# Turnstile_ZpC.net
KiCad netlist of a schematic drawn in EAGLE
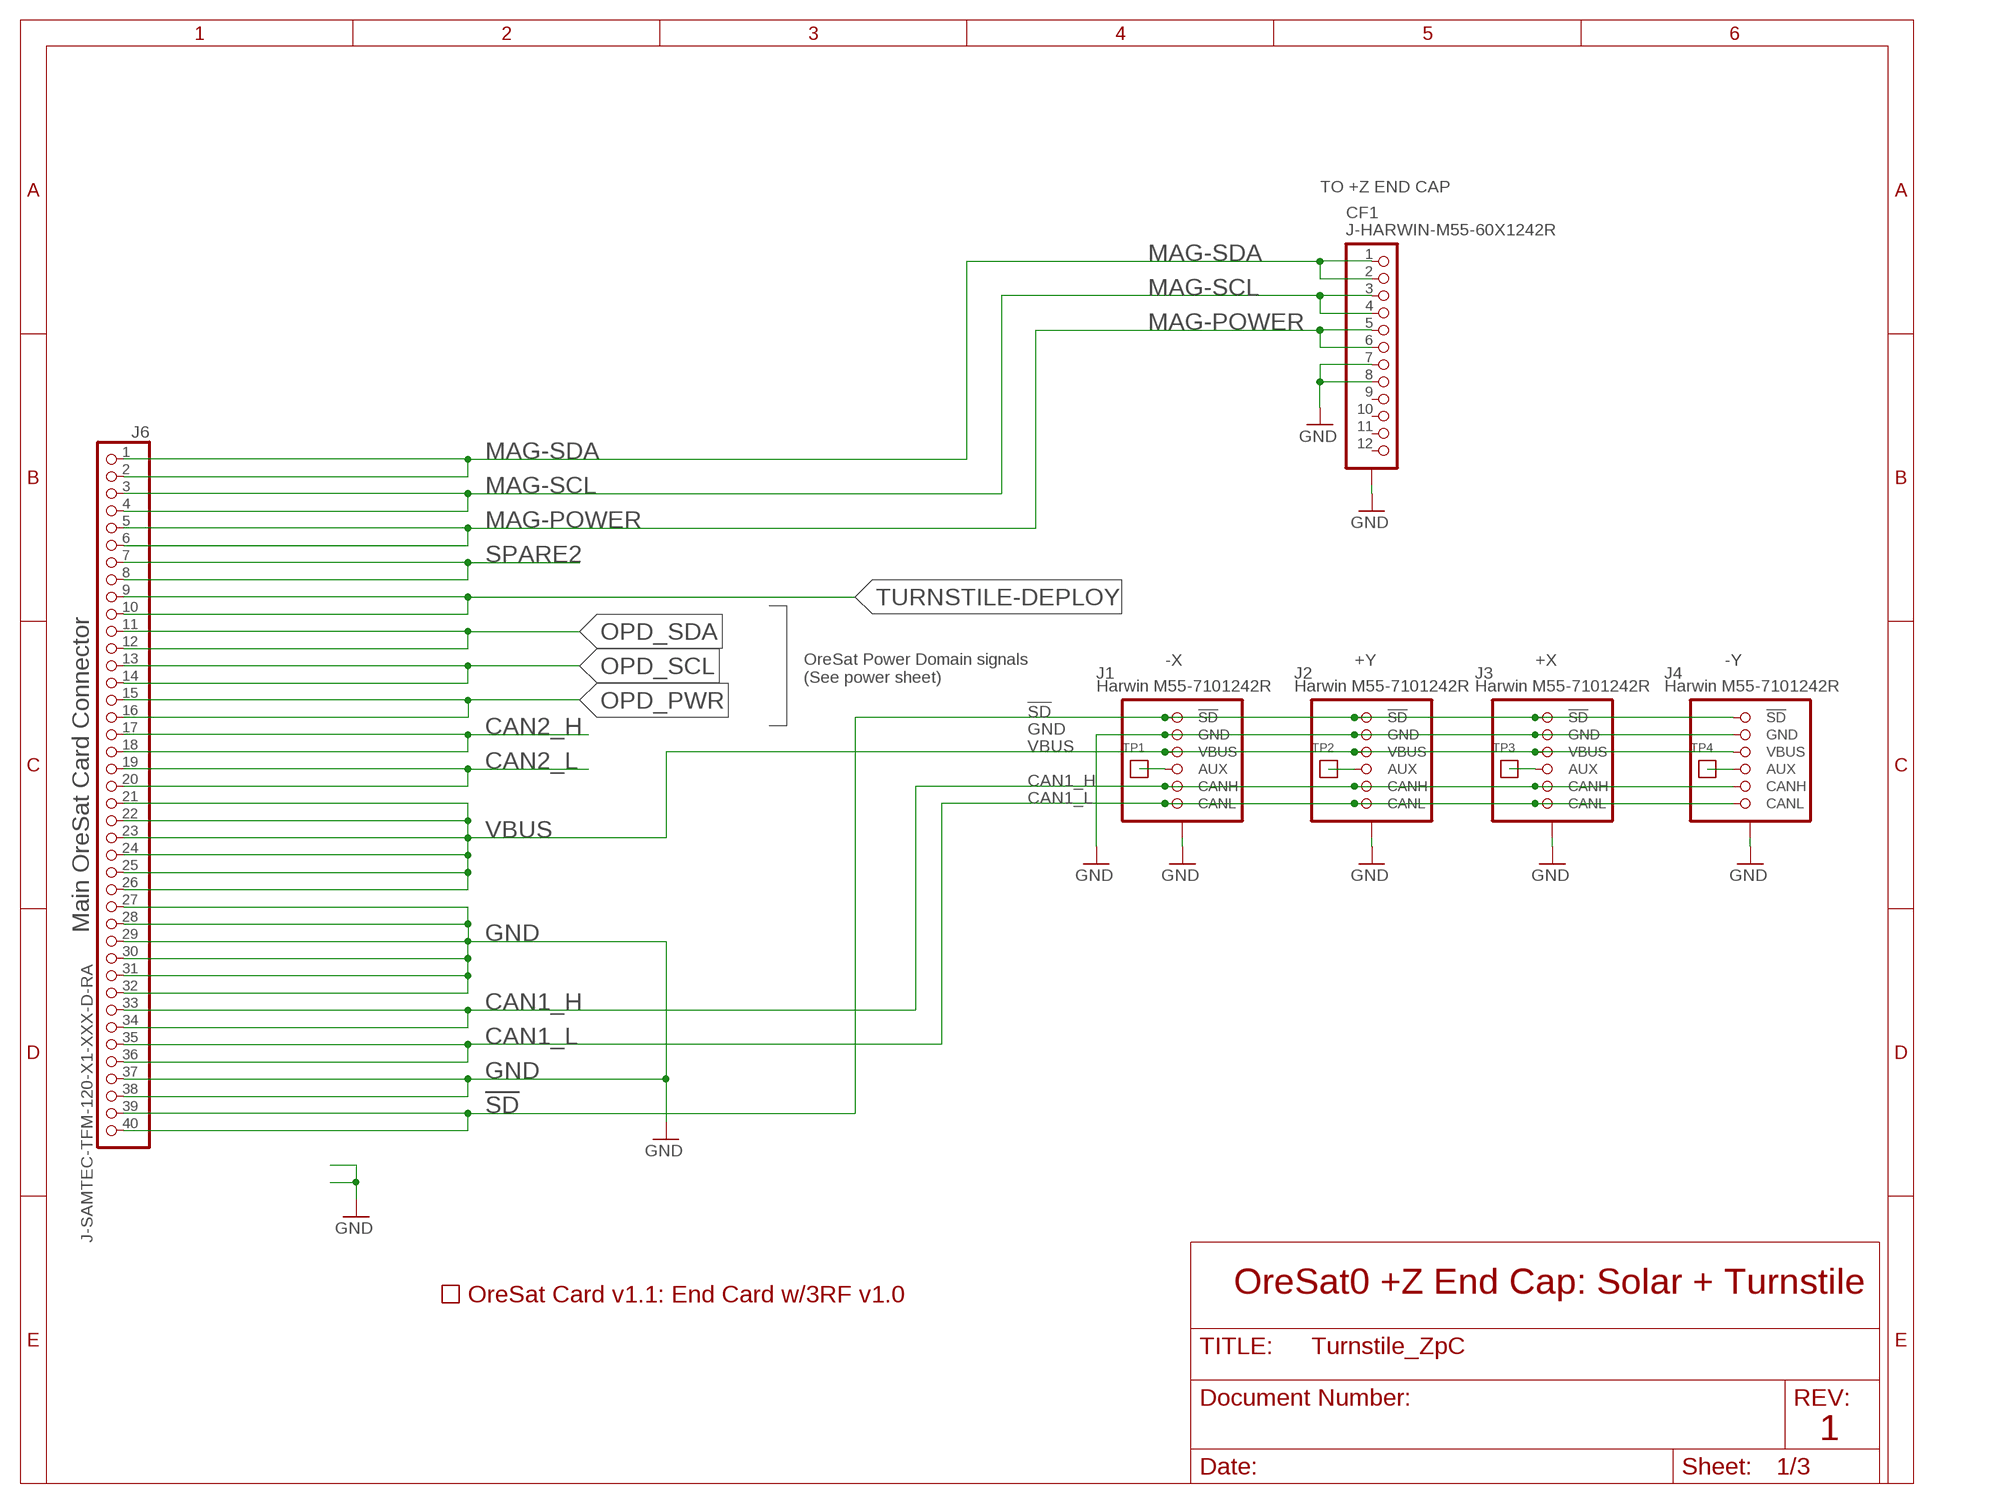
[diagram p0: schematic, sheet 1]
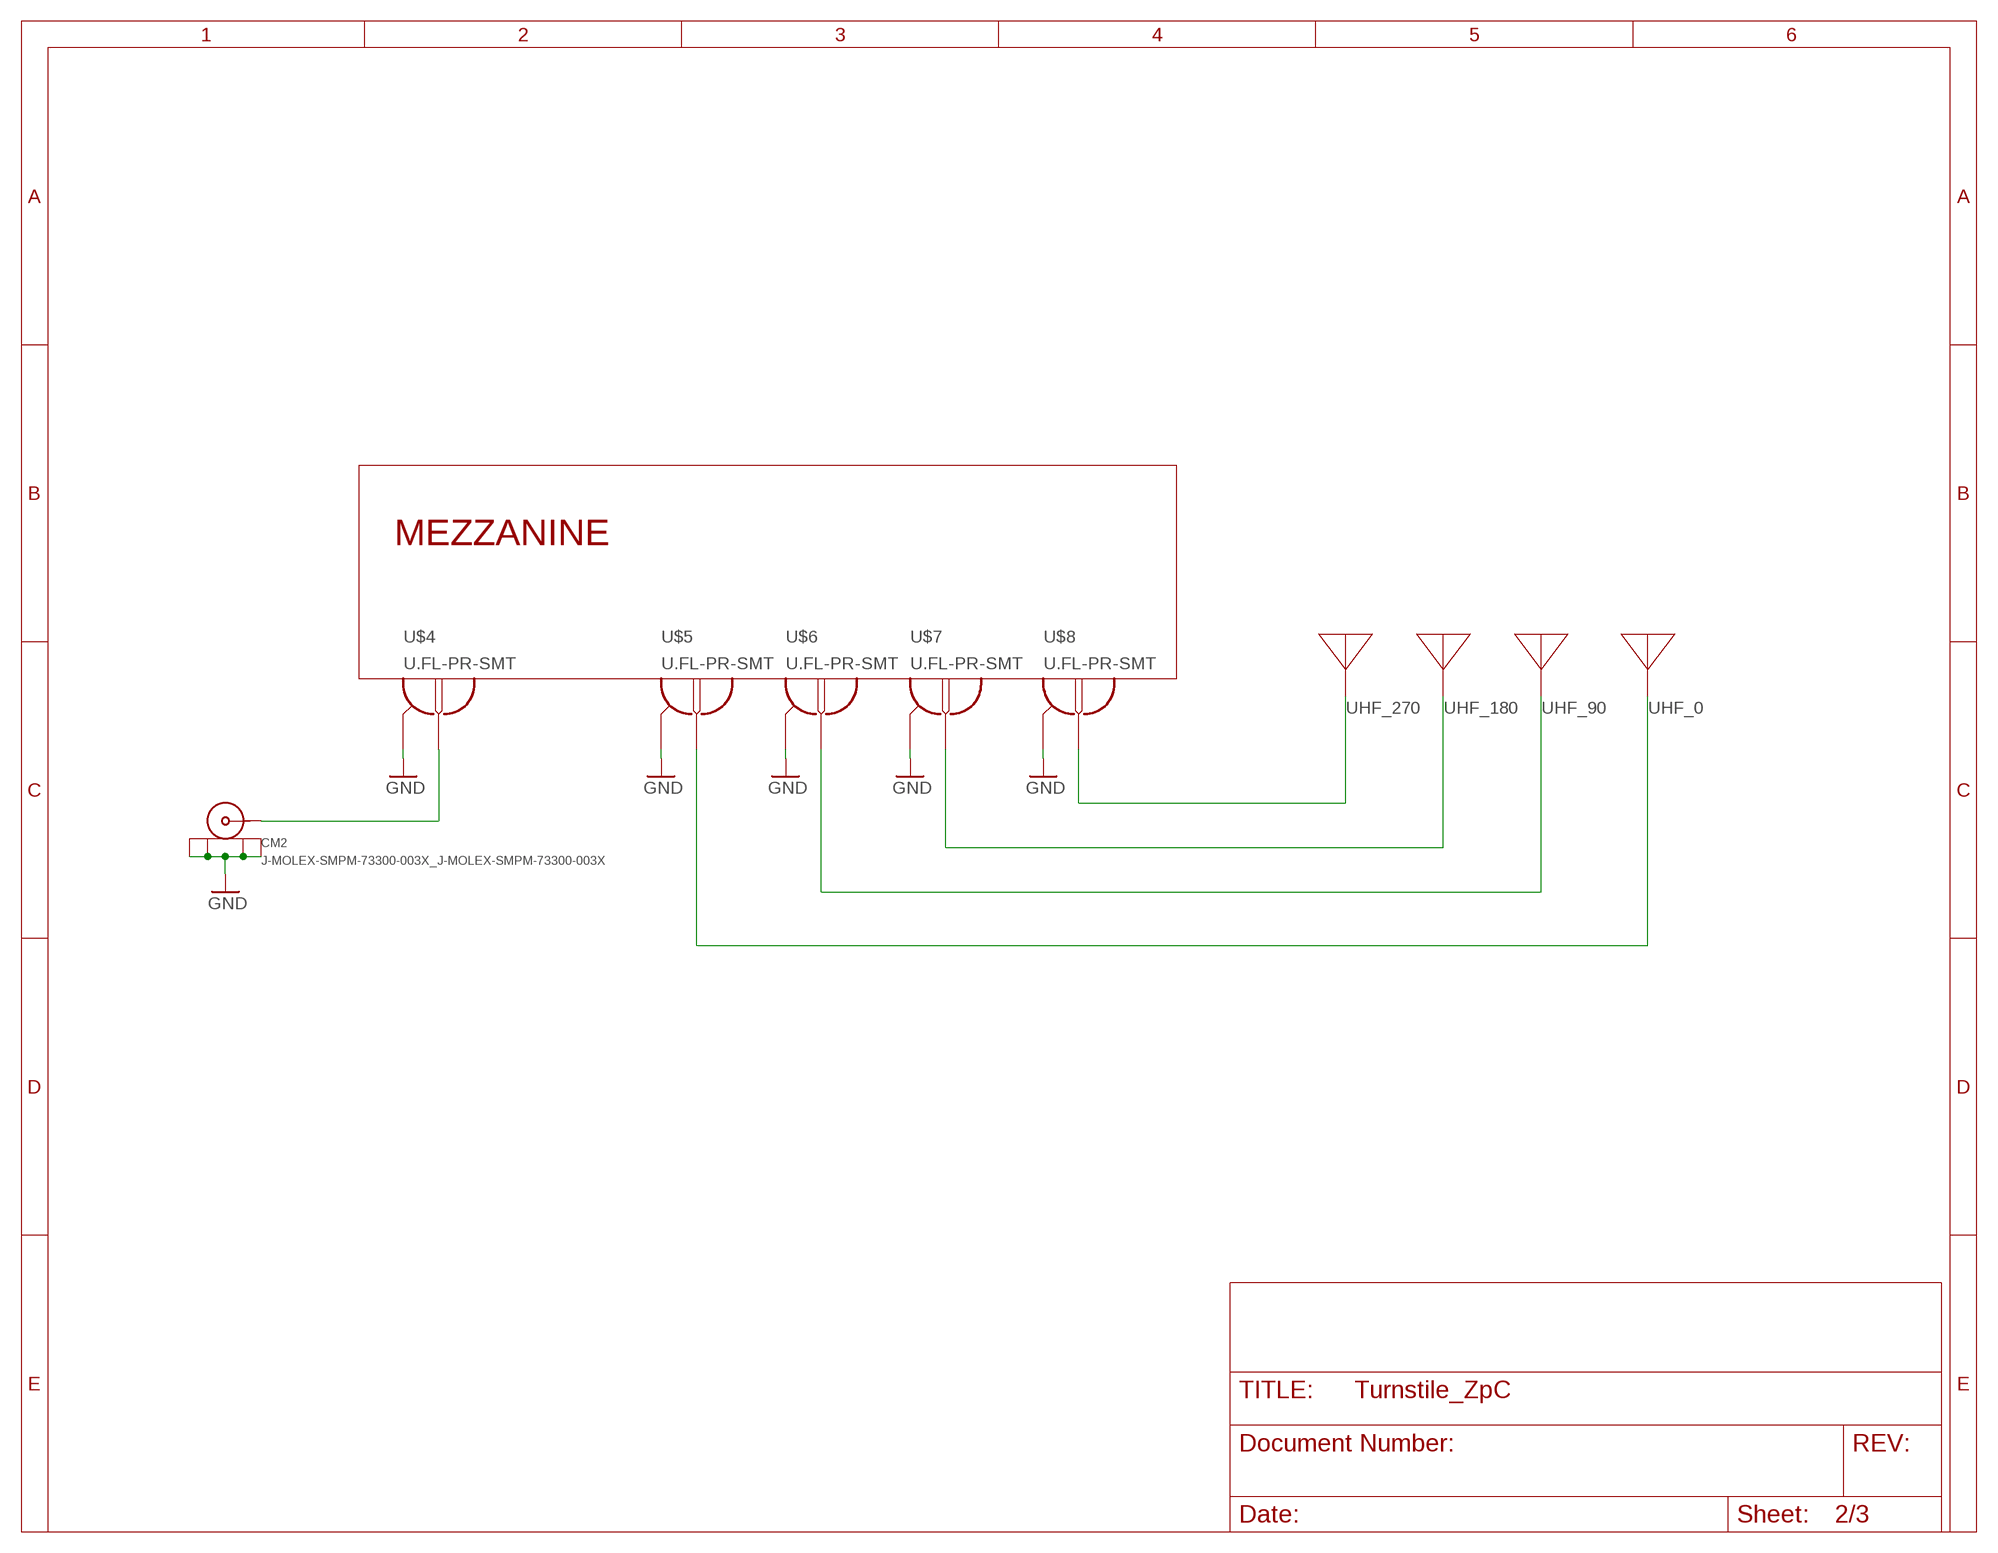
[diagram p1: schematic, sheet 2]
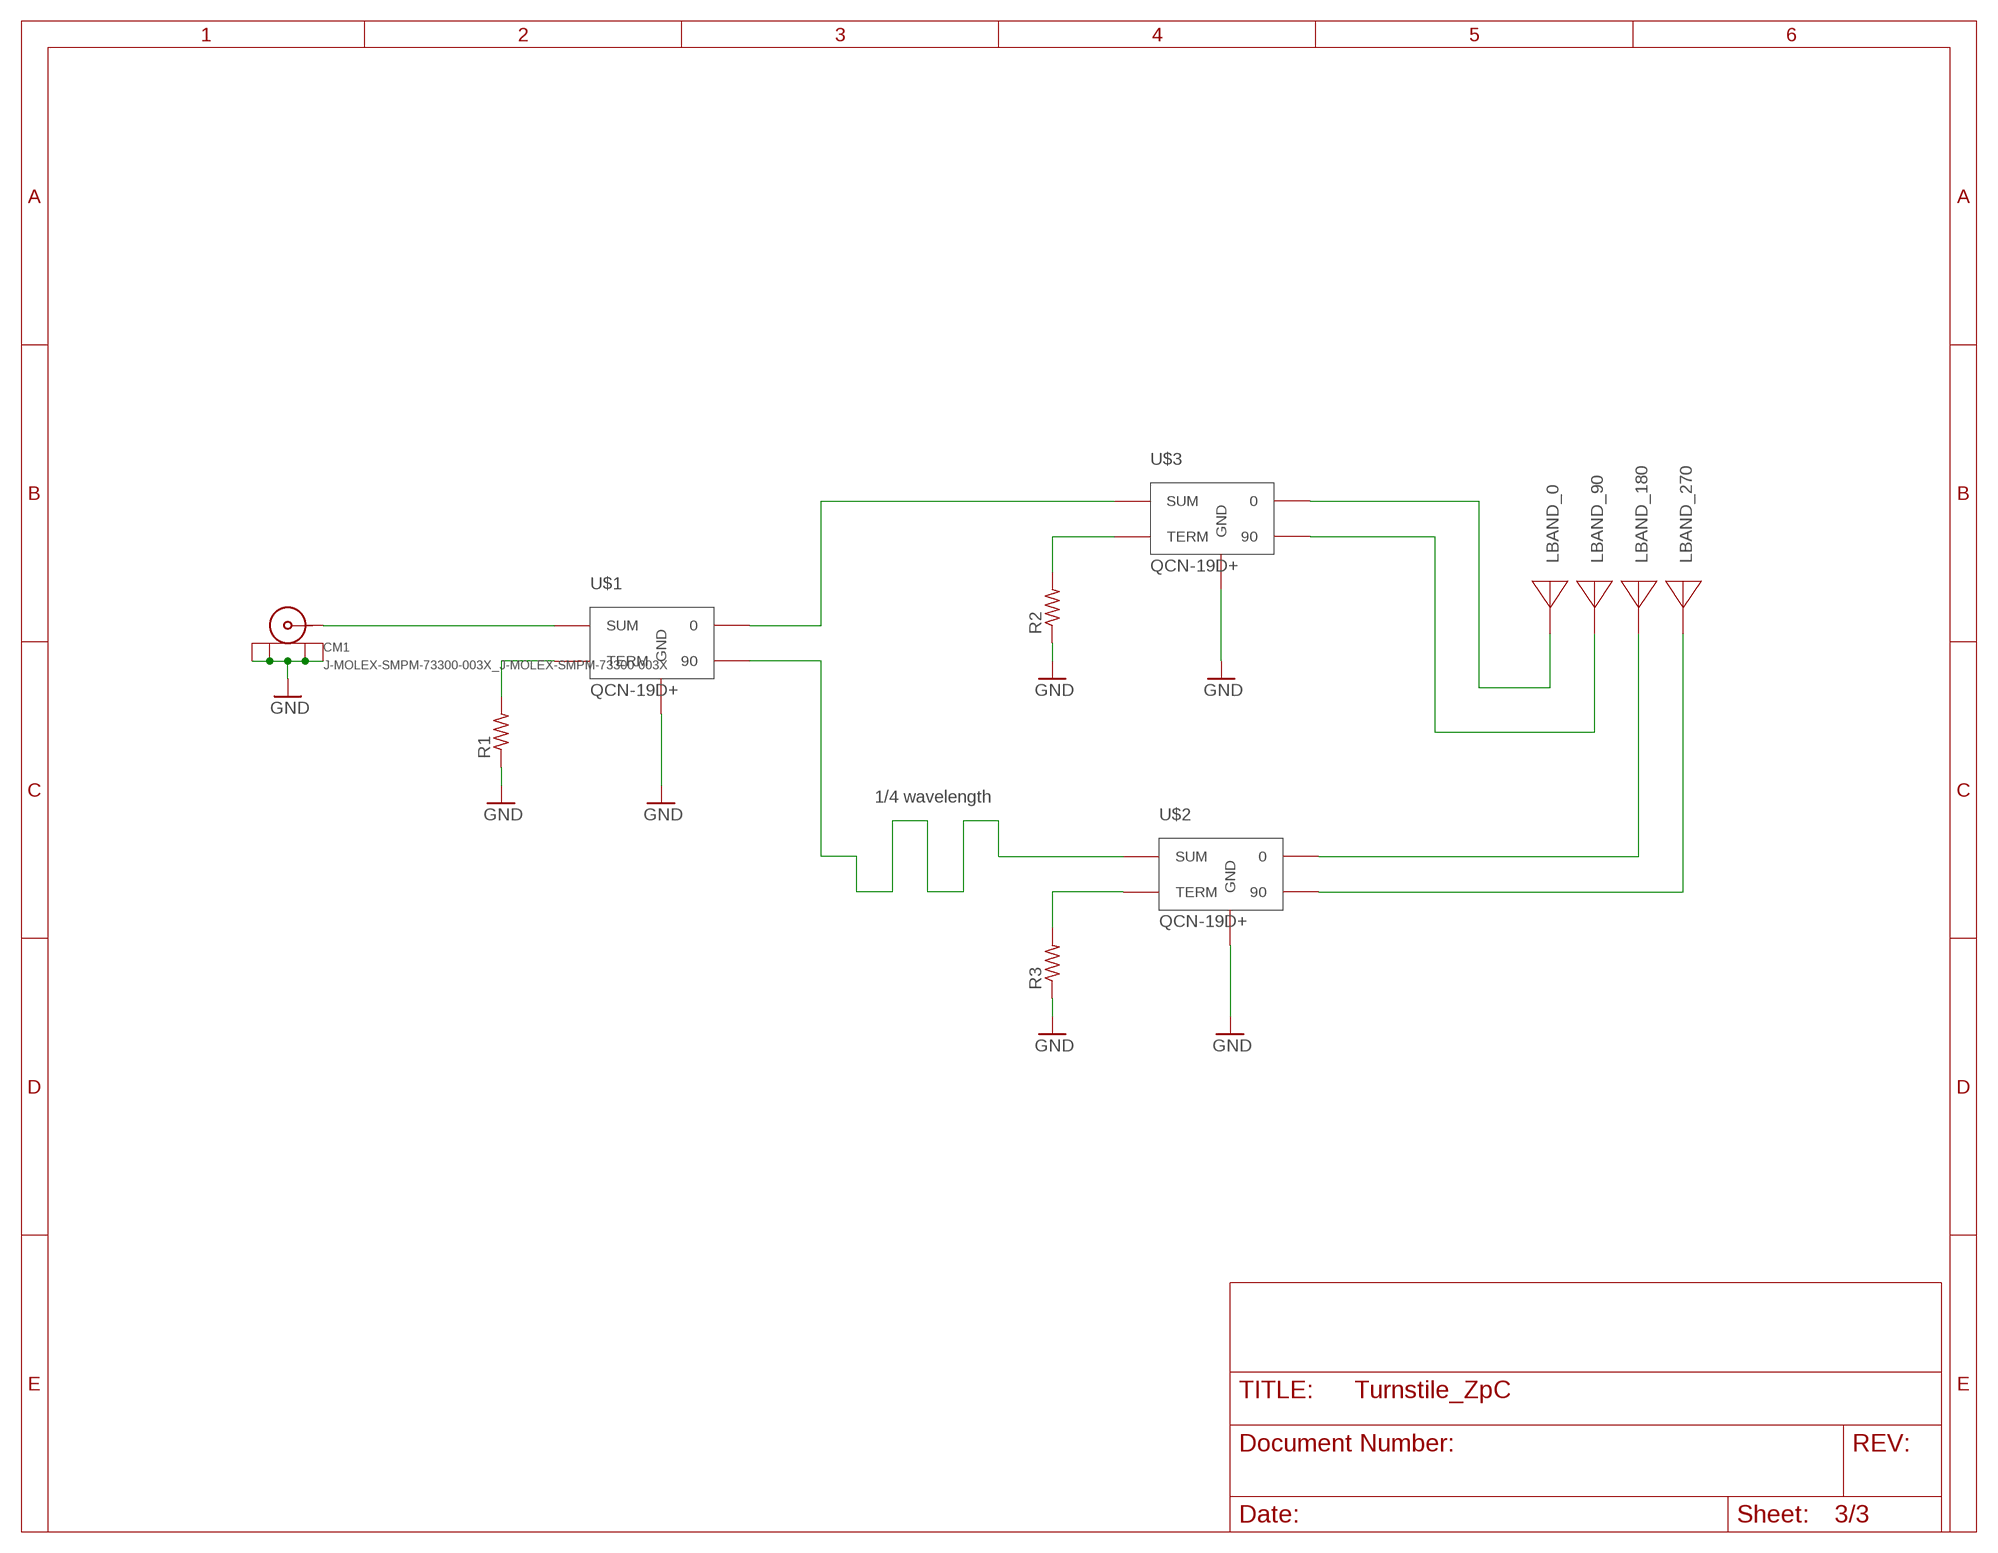
[diagram p2: schematic, sheet 3]

(export (version "E")
  (design (tool "Eeschema 10.0.6"))
  (components
    (comp (ref "CM1")
      (value "J-MOLEX-SMPM-73300-003X_J-MOLEX-SMPM-73300-003X")
      (footprint "eagle-import:J-MOLEX-SMPM-73300-003X_J-MOLEX-SMPM-073300-003X")
      (libsource (lib "eagle-import") (part "J-MOLEX-SMPM-73300-003X_J-MOLEX-SMPM-73300-003X"))
    )
    (comp (ref "R1")
      (value "R-US_0805-B-NOSILK")
      (footprint "eagle-import:.0805-B-NOSILK")
      (libsource (lib "eagle-import") (part "R-US_0805-B-NOSILK"))
    )
    (comp (ref "R2")
      (value "R-US_0805-B-NOSILK")
      (footprint "eagle-import:.0805-B-NOSILK")
      (libsource (lib "eagle-import") (part "R-US_0805-B-NOSILK"))
    )
    (comp (ref "R3")
      (value "R-US_0805-B-NOSILK")
      (footprint "eagle-import:.0805-B-NOSILK")
      (libsource (lib "eagle-import") (part "R-US_0805-B-NOSILK"))
    )
    (comp (ref "U$1")
      (value "QCN-19D+")
      (footprint "eagle-import:QVN-19D+")
      (libsource (lib "eagle-import") (part "QCN-19D+"))
    )
    (comp (ref "U$2")
      (value "QCN-19D+")
      (footprint "eagle-import:QVN-19D+")
      (libsource (lib "eagle-import") (part "QCN-19D+"))
    )
    (comp (ref "U$3")
      (value "QCN-19D+")
      (footprint "eagle-import:QVN-19D+")
      (libsource (lib "eagle-import") (part "QCN-19D+"))
    )
    (comp (ref "CF1")
      (value "J-HARWIN-M55-60X1242R")
      (footprint "eagle-import:HARWIN-M55-60X1242R")
      (libsource (lib "eagle-import") (part "J-HARWIN-M55-60X1242R"))
    )
    (comp (ref "J1")
      (value "Harwin M55-7101242R")
      (footprint "eagle-import:M55-7101242R")
      (libsource (lib "eagle-import") (part "SOLAR-CARD-CONNECTOR"))
    )
    (comp (ref "J2")
      (value "Harwin M55-7101242R")
      (footprint "eagle-import:M55-7101242R")
      (libsource (lib "eagle-import") (part "SOLAR-CARD-CONNECTOR"))
    )
    (comp (ref "J3")
      (value "Harwin M55-7101242R")
      (footprint "eagle-import:M55-7101242R")
      (libsource (lib "eagle-import") (part "SOLAR-CARD-CONNECTOR"))
    )
    (comp (ref "J4")
      (value "Harwin M55-7101242R")
      (footprint "eagle-import:M55-7101242R")
      (libsource (lib "eagle-import") (part "SOLAR-CARD-CONNECTOR"))
    )
    (comp (ref "J6")
      (value "J-SAMTEC-TFM-120-X1-XXX-D-RA")
      (footprint "eagle-import:J-SAMTEC-TFM-120-X1-XXX-D-RA")
      (fields (field (name "MFR") "Samtec") (field (name "MPN") "TFM-120-01-L-D-RA"))
      (libsource (lib "eagle-import") (part "J-SAMTEC-TFM-120-X1-XXX-D-RA"))
    )
    (comp (ref "PCB1")
      (value "ORESAT-CARD-V1.1-END-CARD-3RF-V1.0")
      (footprint "eagle-import:ORESAT-CARDV1.1-END-CARD-3RF-V1.0")
      (libsource (lib "eagle-import") (part "ORESAT-CARD-V1.1-END-CARD-3RF-V1.0"))
    )
    (comp (ref "TP1")
      (value "TEST-POINT-LARGE-SQUARE")
      (footprint "eagle-import:1X01")
      (libsource (lib "eagle-import") (part "TEST-POINT-LARGE-SQUARE"))
    )
    (comp (ref "TP2")
      (value "TEST-POINT-LARGE-SQUARE")
      (footprint "eagle-import:1X01")
      (libsource (lib "eagle-import") (part "TEST-POINT-LARGE-SQUARE"))
    )
    (comp (ref "TP3")
      (value "TEST-POINT-LARGE-SQUARE")
      (footprint "eagle-import:1X01")
      (libsource (lib "eagle-import") (part "TEST-POINT-LARGE-SQUARE"))
    )
    (comp (ref "TP4")
      (value "TEST-POINT-LARGE-SQUARE")
      (footprint "eagle-import:1X01")
      (libsource (lib "eagle-import") (part "TEST-POINT-LARGE-SQUARE"))
    )
    (comp (ref "CM2")
      (value "J-MOLEX-SMPM-73300-003X_J-MOLEX-SMPM-73300-003X")
      (footprint "eagle-import:J-MOLEX-SMPM-73300-003X_J-MOLEX-SMPM-073300-003X")
      (libsource (lib "eagle-import") (part "J-MOLEX-SMPM-73300-003X_J-MOLEX-SMPM-73300-003X"))
    )
    (comp (ref "U$4")
      (value "U.FL-PR-SMT")
      (footprint "eagle-import:U.FL-PR-SMT")
      (libsource (lib "eagle-import") (part "U.FL-PR-SMT"))
    )
    (comp (ref "U$5")
      (value "U.FL-PR-SMT")
      (footprint "eagle-import:U.FL-PR-SMT")
      (libsource (lib "eagle-import") (part "U.FL-PR-SMT"))
    )
    (comp (ref "U$6")
      (value "U.FL-PR-SMT")
      (footprint "eagle-import:U.FL-PR-SMT")
      (libsource (lib "eagle-import") (part "U.FL-PR-SMT"))
    )
    (comp (ref "U$7")
      (value "U.FL-PR-SMT")
      (footprint "eagle-import:U.FL-PR-SMT")
      (libsource (lib "eagle-import") (part "U.FL-PR-SMT"))
    )
    (comp (ref "U$8")
      (value "U.FL-PR-SMT")
      (footprint "eagle-import:U.FL-PR-SMT")
      (libsource (lib "eagle-import") (part "U.FL-PR-SMT"))
    )
  )
  (nets
    (net (code "1") (name "CAN1_H") (class "Default")
      (node (ref "J1") (pin "10") (pinfunction "CANH_10") (pintype "passive"))
      (node (ref "J1") (pin "9") (pinfunction "CANH_9") (pintype "passive"))
      (node (ref "J2") (pin "10") (pinfunction "CANH_10") (pintype "passive"))
      (node (ref "J2") (pin "9") (pinfunction "CANH_9") (pintype "passive"))
      (node (ref "J3") (pin "10") (pinfunction "CANH_10") (pintype "passive"))
      (node (ref "J3") (pin "9") (pinfunction "CANH_9") (pintype "passive"))
      (node (ref "J4") (pin "10") (pinfunction "CANH_10") (pintype "passive"))
      (node (ref "J4") (pin "9") (pinfunction "CANH_9") (pintype "passive"))
      (node (ref "J6") (pin "33") (pinfunction "33_33") (pintype "passive"))
      (node (ref "J6") (pin "34") (pinfunction "34_34") (pintype "passive"))
    )
    (net (code "2") (name "CAN1_L") (class "Default")
      (node (ref "J1") (pin "11") (pinfunction "CANL_11") (pintype "passive"))
      (node (ref "J1") (pin "12") (pinfunction "CANL_12") (pintype "passive"))
      (node (ref "J2") (pin "11") (pinfunction "CANL_11") (pintype "passive"))
      (node (ref "J2") (pin "12") (pinfunction "CANL_12") (pintype "passive"))
      (node (ref "J3") (pin "11") (pinfunction "CANL_11") (pintype "passive"))
      (node (ref "J3") (pin "12") (pinfunction "CANL_12") (pintype "passive"))
      (node (ref "J4") (pin "11") (pinfunction "CANL_11") (pintype "passive"))
      (node (ref "J4") (pin "12") (pinfunction "CANL_12") (pintype "passive"))
      (node (ref "J6") (pin "35") (pinfunction "35_35") (pintype "passive"))
      (node (ref "J6") (pin "36") (pinfunction "36_36") (pintype "passive"))
    )
    (net (code "3") (name "CAN2_H") (class "Default")
      (node (ref "J6") (pin "17") (pinfunction "17_17") (pintype "passive"))
      (node (ref "J6") (pin "18") (pinfunction "18_18") (pintype "passive"))
    )
    (net (code "4") (name "CAN2_L") (class "Default")
      (node (ref "J6") (pin "19") (pinfunction "19_19") (pintype "passive"))
      (node (ref "J6") (pin "20") (pinfunction "20_20") (pintype "passive"))
    )
    (net (code "5") (name "GND") (class "Default")
      (node (ref "CF1") (pin "7") (pinfunction "7_7") (pintype "passive"))
      (node (ref "CF1") (pin "8") (pinfunction "8_8") (pintype "passive"))
      (node (ref "CF1") (pin "P$1") (pinfunction "SHIELDS_P$1") (pintype "passive"))
      (node (ref "CF1") (pin "P$2") (pinfunction "SHIELDS_P$2") (pintype "passive"))
      (node (ref "CF1") (pin "P$3") (pinfunction "SHIELDS_P$3") (pintype "passive"))
      (node (ref "CF1") (pin "P$4") (pinfunction "SHIELDS_P$4") (pintype "passive"))
      (node (ref "CM1") (pin "P$1") (pinfunction "SHIELD3_P$1") (pintype "passive"))
      (node (ref "CM1") (pin "P$2") (pinfunction "SHIELD2_P$2") (pintype "passive"))
      (node (ref "CM1") (pin "P$3") (pinfunction "SHIELD1_P$3") (pintype "passive"))
      (node (ref "CM1") (pin "P$4") (pinfunction "SHIELD_P$4") (pintype "passive"))
      (node (ref "CM2") (pin "P$1") (pinfunction "SHIELD3_P$1") (pintype "passive"))
      (node (ref "CM2") (pin "P$2") (pinfunction "SHIELD2_P$2") (pintype "passive"))
      (node (ref "CM2") (pin "P$3") (pinfunction "SHIELD1_P$3") (pintype "passive"))
      (node (ref "CM2") (pin "P$4") (pinfunction "SHIELD_P$4") (pintype "passive"))
      (node (ref "J1") (pin "3") (pinfunction "GND_3") (pintype "passive"))
      (node (ref "J1") (pin "4") (pinfunction "GND_4") (pintype "passive"))
      (node (ref "J1") (pin "P$1") (pinfunction "SHIELD_P$1") (pintype "passive"))
      (node (ref "J1") (pin "P$2") (pinfunction "SHIELD_P$2") (pintype "passive"))
      (node (ref "J1") (pin "P$3") (pinfunction "SHIELD_P$3") (pintype "passive"))
      (node (ref "J1") (pin "P$4") (pinfunction "SHIELD_P$4") (pintype "passive"))
      (node (ref "J2") (pin "3") (pinfunction "GND_3") (pintype "passive"))
      (node (ref "J2") (pin "4") (pinfunction "GND_4") (pintype "passive"))
      (node (ref "J2") (pin "P$1") (pinfunction "SHIELD_P$1") (pintype "passive"))
      (node (ref "J2") (pin "P$2") (pinfunction "SHIELD_P$2") (pintype "passive"))
      (node (ref "J2") (pin "P$3") (pinfunction "SHIELD_P$3") (pintype "passive"))
      (node (ref "J2") (pin "P$4") (pinfunction "SHIELD_P$4") (pintype "passive"))
      (node (ref "J3") (pin "3") (pinfunction "GND_3") (pintype "passive"))
      (node (ref "J3") (pin "4") (pinfunction "GND_4") (pintype "passive"))
      (node (ref "J3") (pin "P$1") (pinfunction "SHIELD_P$1") (pintype "passive"))
      (node (ref "J3") (pin "P$2") (pinfunction "SHIELD_P$2") (pintype "passive"))
      (node (ref "J3") (pin "P$3") (pinfunction "SHIELD_P$3") (pintype "passive"))
      (node (ref "J3") (pin "P$4") (pinfunction "SHIELD_P$4") (pintype "passive"))
      (node (ref "J4") (pin "3") (pinfunction "GND_3") (pintype "passive"))
      (node (ref "J4") (pin "4") (pinfunction "GND_4") (pintype "passive"))
      (node (ref "J4") (pin "P$1") (pinfunction "SHIELD_P$1") (pintype "passive"))
      (node (ref "J4") (pin "P$2") (pinfunction "SHIELD_P$2") (pintype "passive"))
      (node (ref "J4") (pin "P$3") (pinfunction "SHIELD_P$3") (pintype "passive"))
      (node (ref "J4") (pin "P$4") (pinfunction "SHIELD_P$4") (pintype "passive"))
      (node (ref "J6") (pin "27") (pinfunction "27_27") (pintype "passive"))
      (node (ref "J6") (pin "28") (pinfunction "28_28") (pintype "passive"))
      (node (ref "J6") (pin "29") (pinfunction "29_29") (pintype "passive"))
      (node (ref "J6") (pin "30") (pinfunction "30_30") (pintype "passive"))
      (node (ref "J6") (pin "31") (pinfunction "31_31") (pintype "passive"))
      (node (ref "J6") (pin "32") (pinfunction "32_32") (pintype "passive"))
      (node (ref "J6") (pin "37") (pinfunction "37_37") (pintype "passive"))
      (node (ref "J6") (pin "38") (pinfunction "38_38") (pintype "passive"))
      (node (ref "R1") (pin "1") (pinfunction "1_1") (pintype "passive"))
      (node (ref "R2") (pin "1") (pinfunction "1_1") (pintype "passive"))
      (node (ref "R3") (pin "1") (pinfunction "1_1") (pintype "passive"))
      (node (ref "U$1") (pin "P$2") (pinfunction "GND_P$2") (pintype "bidirectional"))
      (node (ref "U$1") (pin "P$5") (pinfunction "GND_P$5") (pintype "bidirectional"))
      (node (ref "U$2") (pin "P$2") (pinfunction "GND_P$2") (pintype "bidirectional"))
      (node (ref "U$2") (pin "P$5") (pinfunction "GND_P$5") (pintype "bidirectional"))
      (node (ref "U$3") (pin "P$2") (pinfunction "GND_P$2") (pintype "bidirectional"))
      (node (ref "U$3") (pin "P$5") (pinfunction "GND_P$5") (pintype "bidirectional"))
      (node (ref "U$4") (pin "P$2") (pinfunction "P$2_P$2") (pintype "bidirectional"))
      (node (ref "U$4") (pin "P$3") (pinfunction "P$2_P$3") (pintype "bidirectional"))
      (node (ref "U$5") (pin "P$2") (pinfunction "P$2_P$2") (pintype "bidirectional"))
      (node (ref "U$5") (pin "P$3") (pinfunction "P$2_P$3") (pintype "bidirectional"))
      (node (ref "U$6") (pin "P$2") (pinfunction "P$2_P$2") (pintype "bidirectional"))
      (node (ref "U$6") (pin "P$3") (pinfunction "P$2_P$3") (pintype "bidirectional"))
      (node (ref "U$7") (pin "P$2") (pinfunction "P$2_P$2") (pintype "bidirectional"))
      (node (ref "U$7") (pin "P$3") (pinfunction "P$2_P$3") (pintype "bidirectional"))
      (node (ref "U$8") (pin "P$2") (pinfunction "P$2_P$2") (pintype "bidirectional"))
      (node (ref "U$8") (pin "P$3") (pinfunction "P$2_P$3") (pintype "bidirectional"))
    )
    (net (code "6") (name "LBAND_0") (class "Default")
      (node (ref "U$3") (pin "P$4") (pinfunction "0_P$4") (pintype "bidirectional"))
    )
    (net (code "7") (name "LBAND_90") (class "Default")
      (node (ref "U$3") (pin "P$6") (pinfunction "90_P$6") (pintype "bidirectional"))
    )
    (net (code "8") (name "LBAND_180") (class "Default")
      (node (ref "U$2") (pin "P$4") (pinfunction "0_P$4") (pintype "bidirectional"))
    )
    (net (code "9") (name "LBAND_270") (class "Default")
      (node (ref "U$2") (pin "P$6") (pinfunction "90_P$6") (pintype "bidirectional"))
    )
    (net (code "10") (name "MAG-POWER") (class "Default")
      (node (ref "CF1") (pin "5") (pinfunction "5_5") (pintype "passive"))
      (node (ref "CF1") (pin "6") (pinfunction "6_6") (pintype "passive"))
      (node (ref "J6") (pin "5") (pinfunction "5_5") (pintype "passive"))
      (node (ref "J6") (pin "6") (pinfunction "6_6") (pintype "passive"))
    )
    (net (code "11") (name "MAG-SCL") (class "Default")
      (node (ref "CF1") (pin "3") (pinfunction "3_3") (pintype "passive"))
      (node (ref "CF1") (pin "4") (pinfunction "4_4") (pintype "passive"))
      (node (ref "J6") (pin "3") (pinfunction "3_3") (pintype "passive"))
      (node (ref "J6") (pin "4") (pinfunction "4_4") (pintype "passive"))
    )
    (net (code "12") (name "MAG-SDA") (class "Default")
      (node (ref "CF1") (pin "1") (pinfunction "1_1") (pintype "passive"))
      (node (ref "CF1") (pin "2") (pinfunction "2_2") (pintype "passive"))
      (node (ref "J6") (pin "1") (pinfunction "1_1") (pintype "passive"))
      (node (ref "J6") (pin "2") (pinfunction "2_2") (pintype "passive"))
    )
    (net (code "13") (name "Net-(CM1-CENTER)") (class "Default")
      (node (ref "CM1") (pin "RF") (pinfunction "CENTER_RF") (pintype "passive"))
      (node (ref "U$1") (pin "P$1") (pinfunction "SUM_P$1") (pintype "bidirectional"))
    )
    (net (code "14") (name "Net-(CM2-CENTER)") (class "Default")
      (node (ref "CM2") (pin "RF") (pinfunction "CENTER_RF") (pintype "passive"))
      (node (ref "U$4") (pin "P$1") (pinfunction "P$1_P$1") (pintype "bidirectional"))
    )
    (net (code "15") (name "Net-(J1-AUX-Pad7)") (class "Default")
      (node (ref "J1") (pin "7") (pinfunction "AUX_7") (pintype "passive"))
      (node (ref "J1") (pin "8") (pinfunction "AUX_8") (pintype "passive"))
      (node (ref "TP1") (pin "1") (pinfunction "1_1") (pintype "passive"))
    )
    (net (code "16") (name "Net-(J2-AUX-Pad7)") (class "Default")
      (node (ref "J2") (pin "7") (pinfunction "AUX_7") (pintype "passive"))
      (node (ref "J2") (pin "8") (pinfunction "AUX_8") (pintype "passive"))
      (node (ref "TP2") (pin "1") (pinfunction "1_1") (pintype "passive"))
    )
    (net (code "17") (name "Net-(J3-AUX-Pad7)") (class "Default")
      (node (ref "J3") (pin "7") (pinfunction "AUX_7") (pintype "passive"))
      (node (ref "J3") (pin "8") (pinfunction "AUX_8") (pintype "passive"))
      (node (ref "TP3") (pin "1") (pinfunction "1_1") (pintype "passive"))
    )
    (net (code "18") (name "Net-(J4-AUX-Pad7)") (class "Default")
      (node (ref "J4") (pin "7") (pinfunction "AUX_7") (pintype "passive"))
      (node (ref "J4") (pin "8") (pinfunction "AUX_8") (pintype "passive"))
      (node (ref "TP4") (pin "1") (pinfunction "1_1") (pintype "passive"))
    )
    (net (code "19") (name "Net-(U$1-0)") (class "Default")
      (node (ref "U$1") (pin "P$4") (pinfunction "0_P$4") (pintype "bidirectional"))
      (node (ref "U$3") (pin "P$1") (pinfunction "SUM_P$1") (pintype "bidirectional"))
    )
    (net (code "20") (name "Net-(U$1-90)") (class "Default")
      (node (ref "U$1") (pin "P$6") (pinfunction "90_P$6") (pintype "bidirectional"))
      (node (ref "U$2") (pin "P$1") (pinfunction "SUM_P$1") (pintype "bidirectional"))
    )
    (net (code "21") (name "Net-(U$1-TERM)") (class "Default")
      (node (ref "R1") (pin "2") (pinfunction "2_2") (pintype "passive"))
      (node (ref "U$1") (pin "P$3") (pinfunction "TERM_P$3") (pintype "bidirectional"))
    )
    (net (code "22") (name "Net-(U$2-TERM)") (class "Default")
      (node (ref "R3") (pin "2") (pinfunction "2_2") (pintype "passive"))
      (node (ref "U$2") (pin "P$3") (pinfunction "TERM_P$3") (pintype "bidirectional"))
    )
    (net (code "23") (name "Net-(U$3-TERM)") (class "Default")
      (node (ref "R2") (pin "2") (pinfunction "2_2") (pintype "passive"))
      (node (ref "U$3") (pin "P$3") (pinfunction "TERM_P$3") (pintype "bidirectional"))
    )
    (net (code "24") (name "OPD_PWR") (class "Default")
      (node (ref "J6") (pin "15") (pinfunction "15_15") (pintype "passive"))
      (node (ref "J6") (pin "16") (pinfunction "16_16") (pintype "passive"))
    )
    (net (code "25") (name "OPD_SCL") (class "Default")
      (node (ref "J6") (pin "13") (pinfunction "13_13") (pintype "passive"))
      (node (ref "J6") (pin "14") (pinfunction "14_14") (pintype "passive"))
    )
    (net (code "26") (name "OPD_SDA") (class "Default")
      (node (ref "J6") (pin "11") (pinfunction "11_11") (pintype "passive"))
      (node (ref "J6") (pin "12") (pinfunction "12_12") (pintype "passive"))
    )
    (net (code "27") (name "SPARE2") (class "Default")
      (node (ref "J6") (pin "7") (pinfunction "7_7") (pintype "passive"))
      (node (ref "J6") (pin "8") (pinfunction "8_8") (pintype "passive"))
    )
    (net (code "28") (name "TURNSTILE-DEPLOY") (class "Default")
      (node (ref "J6") (pin "10") (pinfunction "10_10") (pintype "passive"))
      (node (ref "J6") (pin "9") (pinfunction "9_9") (pintype "passive"))
    )
    (net (code "29") (name "UHF_0") (class "Default")
      (node (ref "U$5") (pin "P$1") (pinfunction "P$1_P$1") (pintype "bidirectional"))
    )
    (net (code "30") (name "UHF_90") (class "Default")
      (node (ref "U$6") (pin "P$1") (pinfunction "P$1_P$1") (pintype "bidirectional"))
    )
    (net (code "31") (name "UHF_180") (class "Default")
      (node (ref "U$7") (pin "P$1") (pinfunction "P$1_P$1") (pintype "bidirectional"))
    )
    (net (code "32") (name "UHF_270") (class "Default")
      (node (ref "U$8") (pin "P$1") (pinfunction "P$1_P$1") (pintype "bidirectional"))
    )
    (net (code "33") (name "VBUS") (class "Default")
      (node (ref "J1") (pin "5") (pinfunction "VBUS_5") (pintype "passive"))
      (node (ref "J1") (pin "6") (pinfunction "VBUS_6") (pintype "passive"))
      (node (ref "J2") (pin "5") (pinfunction "VBUS_5") (pintype "passive"))
      (node (ref "J2") (pin "6") (pinfunction "VBUS_6") (pintype "passive"))
      (node (ref "J3") (pin "5") (pinfunction "VBUS_5") (pintype "passive"))
      (node (ref "J3") (pin "6") (pinfunction "VBUS_6") (pintype "passive"))
      (node (ref "J4") (pin "5") (pinfunction "VBUS_5") (pintype "passive"))
      (node (ref "J4") (pin "6") (pinfunction "VBUS_6") (pintype "passive"))
      (node (ref "J6") (pin "21") (pinfunction "21_21") (pintype "passive"))
      (node (ref "J6") (pin "22") (pinfunction "22_22") (pintype "passive"))
      (node (ref "J6") (pin "23") (pinfunction "23_23") (pintype "passive"))
      (node (ref "J6") (pin "24") (pinfunction "24_24") (pintype "passive"))
      (node (ref "J6") (pin "25") (pinfunction "25_25") (pintype "passive"))
      (node (ref "J6") (pin "26") (pinfunction "26_26") (pintype "passive"))
    )
    (net (code "34") (name "unconnected-(CF1-Pad9)") (class "Default")
      (node (ref "CF1") (pin "9") (pinfunction "9_9") (pintype "passive"))
    )
    (net (code "35") (name "unconnected-(CF1-Pad10)") (class "Default")
      (node (ref "CF1") (pin "10") (pinfunction "10_10") (pintype "passive"))
    )
    (net (code "36") (name "unconnected-(CF1-Pad11)") (class "Default")
      (node (ref "CF1") (pin "11") (pinfunction "11_11") (pintype "passive"))
    )
    (net (code "37") (name "unconnected-(CF1-Pad12)") (class "Default")
      (node (ref "CF1") (pin "12") (pinfunction "12_12") (pintype "passive"))
    )
    (net (code "38") (name "~{SD}") (class "Default")
      (node (ref "J1") (pin "1") (pinfunction "~{SD}_1") (pintype "passive"))
      (node (ref "J1") (pin "2") (pinfunction "~{SD}_2") (pintype "passive"))
      (node (ref "J2") (pin "1") (pinfunction "~{SD}_1") (pintype "passive"))
      (node (ref "J2") (pin "2") (pinfunction "~{SD}_2") (pintype "passive"))
      (node (ref "J3") (pin "1") (pinfunction "~{SD}_1") (pintype "passive"))
      (node (ref "J3") (pin "2") (pinfunction "~{SD}_2") (pintype "passive"))
      (node (ref "J4") (pin "1") (pinfunction "~{SD}_1") (pintype "passive"))
      (node (ref "J4") (pin "2") (pinfunction "~{SD}_2") (pintype "passive"))
      (node (ref "J6") (pin "39") (pinfunction "39_39") (pintype "passive"))
      (node (ref "J6") (pin "40") (pinfunction "40_40") (pintype "passive"))
    )
  )
)
